# lis3dsh_spi.net
KiCad netlist of a schematic drawn in Altium Designer
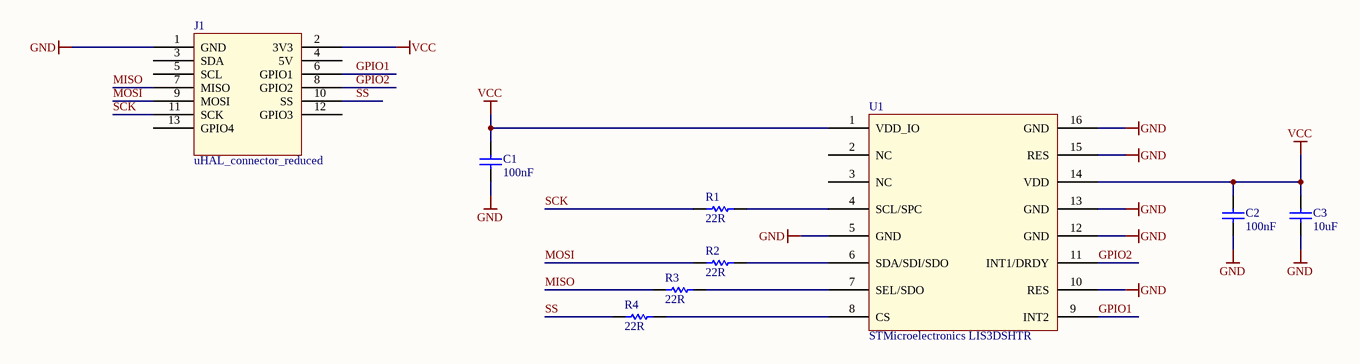
[diagram p0: lis3dsh_spi.SchDoc]

(export (version "E")
  (design (tool "Eeschema 10.0.6"))
  (components
    (comp (ref "C1")
      (value "Murata GCM188R71H104KA57D")
      (footprint "CAPC1608X90X35ML10T15")
      (description "CAP CER 0.1UF 50V 10% X7R 0603")
      (fields (field (name "CAPACITANCE") "100nF"))
      (libsource (lib "CommunityVault") (part "CMP-119667-3"))
    )
    (comp (ref "C2")
      (value "Murata GCM188R71H104KA57D")
      (footprint "CAPC1608X90X35ML10T15")
      (description "CAP CER 0.1UF 50V 10% X7R 0603")
      (fields (field (name "CAPACITANCE") "100nF"))
      (libsource (lib "CommunityVault") (part "CMP-119667-3"))
    )
    (comp (ref "C3")
      (value "Murata GCM188R71H104KA57D")
      (footprint "CAPC1608X90X35ML10T15")
      (description "CAP CER 0.1UF 50V 10% X7R 0603")
      (fields (field (name "CAPACITANCE") "10uF"))
      (libsource (lib "CommunityVault") (part "CMP-119667-3"))
    )
    (comp (ref "J1")
      (value "uHAL_connector_reduced")
      (footprint "PCB-45ncoppm4oopozvqifsq-1")
      (description "connector for uHAL with reduced pin number")
      (libsource (lib "CommunityVault") (part "CMP-2q23h2cwhjlfm8s6r7i8-1"))
    )
    (comp (ref "R1")
      (value "22R")
      (footprint "RESC1608X05N")
      (description "RCA Series 0603 0.1 W 0 O Jumper Surface Mount Thick Film Chip Resistor")
      (fields (field (name "MANUFACTURER PART NUMBER") "RCA06030000ZSEA"))
      (libsource (lib "CommunityVault") (part "SYM-31acf99032f6ee6b-1"))
    )
    (comp (ref "R2")
      (value "22R")
      (footprint "RESC1608X05N")
      (description "RCA Series 0603 0.1 W 0 O Jumper Surface Mount Thick Film Chip Resistor")
      (fields (field (name "MANUFACTURER PART NUMBER") "RCA06030000ZSEA"))
      (libsource (lib "CommunityVault") (part "SYM-31acf99032f6ee6b-1"))
    )
    (comp (ref "R3")
      (value "22R")
      (footprint "RESC1608X05N")
      (description "RCA Series 0603 0.1 W 0 O Jumper Surface Mount Thick Film Chip Resistor")
      (fields (field (name "MANUFACTURER PART NUMBER") "RCA06030000ZSEA"))
      (libsource (lib "CommunityVault") (part "SYM-31acf99032f6ee6b-1"))
    )
    (comp (ref "R4")
      (value "22R")
      (footprint "RESC1608X05N")
      (description "RCA Series 0603 0.1 W 0 O Jumper Surface Mount Thick Film Chip Resistor")
      (fields (field (name "MANUFACTURER PART NUMBER") "RCA06030000ZSEA"))
      (libsource (lib "CommunityVault") (part "SYM-31acf99032f6ee6b-1"))
    )
    (comp (ref "U1")
      (value "STMicroelectronics LIS3DSHTR")
      (footprint "STM-LGA-16_M")
      (description "MEMS digital output motion sensor: ultra low-power high performance 3-axes nano accelerometer")
      (libsource (lib "CommunityVault") (part "CMP-40c388997c2c9f04-1"))
    )
  )
  (nets
    (net (code "1") (name "/GPIO1") (class "Default")
      (node (ref "J1") (pin "6") (pinfunction "GPIO1_6") (pintype "passive"))
      (node (ref "U1") (pin "9") (pinfunction "INT2_9") (pintype "passive"))
    )
    (net (code "2") (name "/GPIO2") (class "Default")
      (node (ref "J1") (pin "8") (pinfunction "GPIO2_8") (pintype "passive"))
      (node (ref "U1") (pin "11") (pinfunction "INT1/DRDY_11") (pintype "passive"))
    )
    (net (code "3") (name "/MISO") (class "Default")
      (node (ref "J1") (pin "7") (pinfunction "MISO_7") (pintype "passive"))
      (node (ref "R3") (pin "2") (pinfunction "2_2") (pintype "passive"))
    )
    (net (code "4") (name "/MOSI") (class "Default")
      (node (ref "J1") (pin "9") (pinfunction "MOSI_9") (pintype "passive"))
      (node (ref "R2") (pin "2") (pinfunction "2_2") (pintype "passive"))
    )
    (net (code "5") (name "/SCK") (class "Default")
      (node (ref "J1") (pin "11") (pinfunction "SCK_11") (pintype "passive"))
      (node (ref "R1") (pin "2") (pinfunction "2_2") (pintype "passive"))
    )
    (net (code "6") (name "/SS") (class "Default")
      (node (ref "J1") (pin "10") (pinfunction "SS_10") (pintype "passive"))
      (node (ref "R4") (pin "2") (pinfunction "2_2") (pintype "passive"))
    )
    (net (code "7") (name "GND") (class "Default")
      (node (ref "C1") (pin "2") (pinfunction "2_2") (pintype "passive"))
      (node (ref "C2") (pin "2") (pinfunction "2_2") (pintype "passive"))
      (node (ref "C3") (pin "2") (pinfunction "2_2") (pintype "passive"))
      (node (ref "J1") (pin "1") (pinfunction "GND_1") (pintype "passive"))
      (node (ref "U1") (pin "10") (pinfunction "RES_10") (pintype "passive"))
      (node (ref "U1") (pin "12") (pinfunction "GND_12") (pintype "passive"))
      (node (ref "U1") (pin "13") (pinfunction "GND_13") (pintype "passive"))
      (node (ref "U1") (pin "15") (pinfunction "RES_15") (pintype "passive"))
      (node (ref "U1") (pin "16") (pinfunction "GND_16") (pintype "passive"))
      (node (ref "U1") (pin "5") (pinfunction "GND_5") (pintype "passive"))
    )
    (net (code "8") (name "Net-(U1-CS)") (class "Default")
      (node (ref "R4") (pin "1") (pinfunction "1_1") (pintype "passive"))
      (node (ref "U1") (pin "8") (pinfunction "CS_8") (pintype "passive"))
    )
    (net (code "9") (name "Net-(U1-SCL{slash}SPC)") (class "Default")
      (node (ref "R1") (pin "1") (pinfunction "1_1") (pintype "passive"))
      (node (ref "U1") (pin "4") (pinfunction "SCL/SPC_4") (pintype "passive"))
    )
    (net (code "10") (name "Net-(U1-SDA{slash}SDI{slash}SDO)") (class "Default")
      (node (ref "R2") (pin "1") (pinfunction "1_1") (pintype "passive"))
      (node (ref "U1") (pin "6") (pinfunction "SDA/SDI/SDO_6") (pintype "passive"))
    )
    (net (code "11") (name "Net-(U1-SEL{slash}SDO)") (class "Default")
      (node (ref "R3") (pin "1") (pinfunction "1_1") (pintype "passive"))
      (node (ref "U1") (pin "7") (pinfunction "SEL/SDO_7") (pintype "passive"))
    )
    (net (code "12") (name "VCC") (class "Default")
      (node (ref "C1") (pin "1") (pinfunction "1_1") (pintype "passive"))
      (node (ref "C2") (pin "1") (pinfunction "1_1") (pintype "passive"))
      (node (ref "C3") (pin "1") (pinfunction "1_1") (pintype "passive"))
      (node (ref "J1") (pin "2") (pinfunction "3V3_2") (pintype "passive"))
      (node (ref "U1") (pin "1") (pinfunction "VDD_IO_1") (pintype "passive"))
      (node (ref "U1") (pin "14") (pinfunction "VDD_14") (pintype "passive"))
    )
    (net (code "13") (name "unconnected-(J1-5V-Pad4)") (class "Default")
      (node (ref "J1") (pin "4") (pinfunction "5V_4") (pintype "passive"))
    )
    (net (code "14") (name "unconnected-(J1-GPIO3-Pad12)") (class "Default")
      (node (ref "J1") (pin "12") (pinfunction "GPIO3_12") (pintype "passive"))
    )
    (net (code "15") (name "unconnected-(J1-GPIO4-Pad13)") (class "Default")
      (node (ref "J1") (pin "13") (pinfunction "GPIO4_13") (pintype "passive"))
    )
    (net (code "16") (name "unconnected-(J1-SCL-Pad5)") (class "Default")
      (node (ref "J1") (pin "5") (pinfunction "SCL_5") (pintype "passive"))
    )
    (net (code "17") (name "unconnected-(J1-SDA-Pad3)") (class "Default")
      (node (ref "J1") (pin "3") (pinfunction "SDA_3") (pintype "passive"))
    )
    (net (code "18") (name "unconnected-(U1-NC-Pad2)") (class "Default")
      (node (ref "U1") (pin "2") (pinfunction "NC_2") (pintype "passive"))
    )
    (net (code "19") (name "unconnected-(U1-NC-Pad3)") (class "Default")
      (node (ref "U1") (pin "3") (pinfunction "NC_3") (pintype "passive"))
    )
  )
)
